# wemos_gpio.net
KiCad netlist of a schematic drawn in EAGLE
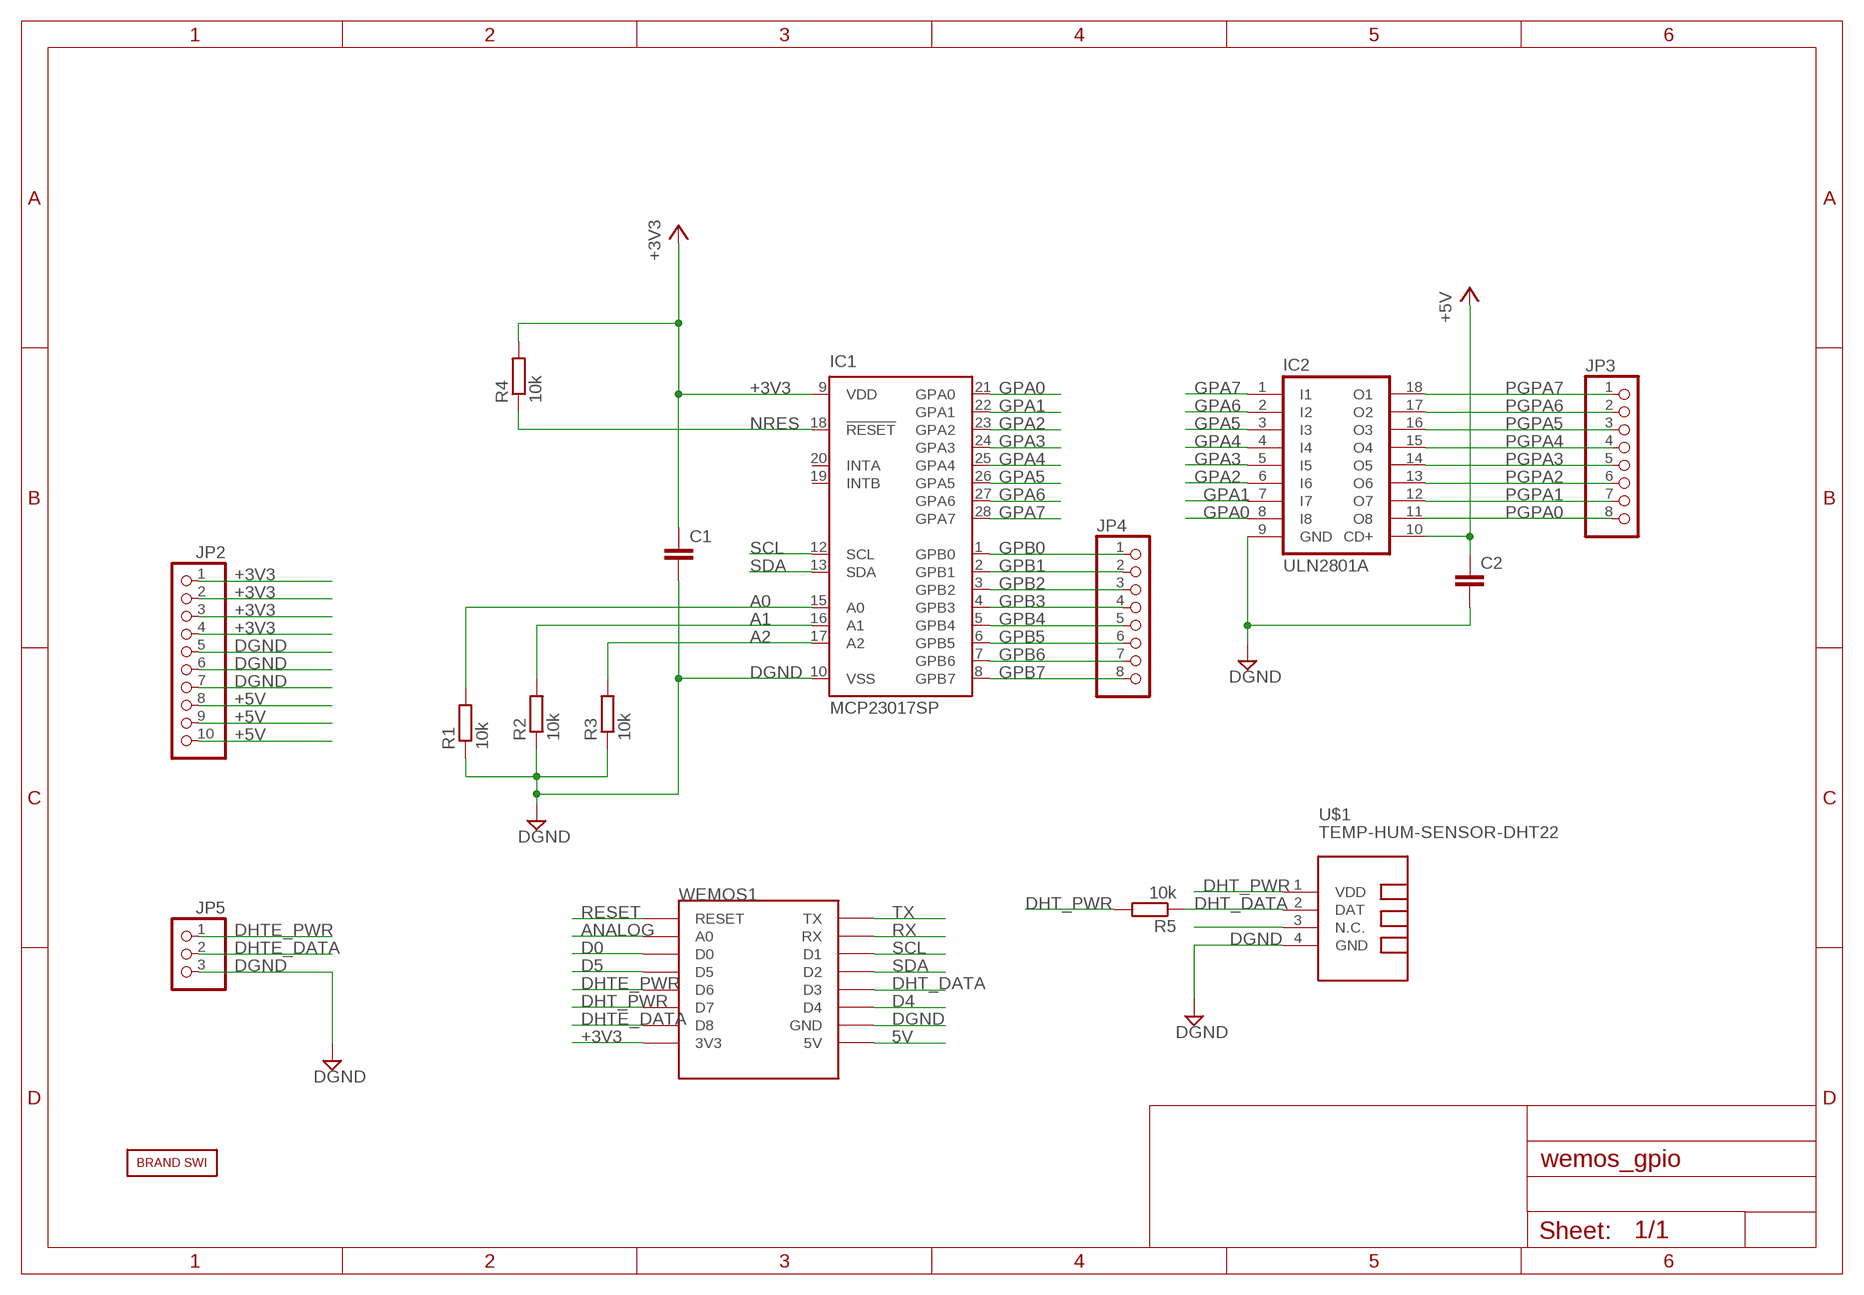
[diagram p0: schematic, sheet 1]

(export (version "E")
  (design (tool "Eeschema 10.0.6"))
  (components
    (comp (ref "C1")
      (value "C-EUC1210")
      (footprint "eagle-import:C1210")
      (libsource (lib "eagle-import") (part "C-EUC1210"))
    )
    (comp (ref "C2")
      (value "C-EUC1210")
      (footprint "eagle-import:C1210")
      (libsource (lib "eagle-import") (part "C-EUC1210"))
    )
    (comp (ref "IC1")
      (value "MCP23017SP")
      (footprint "eagle-import:DIL28-3")
      (fields (field (name "MF") "MICROCHIP") (field (name "MPN") "MCP23017-E/SP"))
      (libsource (lib "eagle-import") (part "MCP23017SP"))
    )
    (comp (ref "IC2")
      (value "ULN2801A")
      (footprint "eagle-import:DIL18")
      (libsource (lib "eagle-import") (part "ULN2801A"))
    )
    (comp (ref "JP2")
      (value "PINHD-1X10")
      (footprint "eagle-import:1X10")
      (libsource (lib "eagle-import") (part "PINHD-1X10"))
    )
    (comp (ref "JP3")
      (value "PINHD-1X8")
      (footprint "eagle-import:1X08")
      (libsource (lib "eagle-import") (part "PINHD-1X8"))
    )
    (comp (ref "JP4")
      (value "PINHD-1X8")
      (footprint "eagle-import:1X08")
      (libsource (lib "eagle-import") (part "PINHD-1X8"))
    )
    (comp (ref "JP5")
      (value "PINHD-1X3")
      (footprint "eagle-import:1X03")
      (libsource (lib "eagle-import") (part "PINHD-1X3"))
    )
    (comp (ref "R1")
      (value "10k")
      (footprint "eagle-import:M1206")
      (libsource (lib "eagle-import") (part "R-EU_M1206"))
    )
    (comp (ref "R2")
      (value "10k")
      (footprint "eagle-import:M1206")
      (libsource (lib "eagle-import") (part "R-EU_M1206"))
    )
    (comp (ref "R3")
      (value "10k")
      (footprint "eagle-import:M1206")
      (libsource (lib "eagle-import") (part "R-EU_M1206"))
    )
    (comp (ref "R4")
      (value "10k")
      (footprint "eagle-import:M1206")
      (libsource (lib "eagle-import") (part "R-EU_M1206"))
    )
    (comp (ref "R5")
      (value "10k")
      (footprint "eagle-import:M1206")
      (libsource (lib "eagle-import") (part "R-EU_M1206"))
    )
    (comp (ref "U$1")
      (value "TEMP-HUM-SENSOR-DHT22")
      (footprint "eagle-import:TEMP-HUM-SENSOR-DHT22")
      (libsource (lib "eagle-import") (part "TEMP-HUM-SENSOR-DHT22"))
    )
    (comp (ref "U$2")
      (value "BRAND_SWI5X7")
      (footprint "eagle-import:BRAND_SWI_5X7")
      (libsource (lib "eagle-import") (part "BRAND_SWI5X7"))
    )
    (comp (ref "WEMOS1")
      (value "WEMOS-D1-MINI")
      (footprint "eagle-import:WEMOS-D1-MINI")
      (libsource (lib "eagle-import") (part "WEMOS-D1-MINI"))
    )
  )
  (nets
    (net (code "1") (name "+3V3") (class "Default")
      (node (ref "C1") (pin "1") (pinfunction "1_1") (pintype "passive"))
      (node (ref "IC1") (pin "9") (pinfunction "VDD_9") (pintype "power_in"))
      (node (ref "JP2") (pin "1") (pinfunction "1_1") (pintype "passive"))
      (node (ref "JP2") (pin "2") (pinfunction "2_2") (pintype "passive"))
      (node (ref "JP2") (pin "3") (pinfunction "3_3") (pintype "passive"))
      (node (ref "JP2") (pin "4") (pinfunction "4_4") (pintype "passive"))
      (node (ref "R4") (pin "2") (pinfunction "2_2") (pintype "passive"))
      (node (ref "WEMOS1") (pin "3V3") (pinfunction "3V3_3V3") (pintype "bidirectional"))
    )
    (net (code "2") (name "+5V") (class "Default")
      (node (ref "C2") (pin "1") (pinfunction "1_1") (pintype "passive"))
      (node (ref "IC2") (pin "10") (pinfunction "CD+_10") (pintype "passive"))
      (node (ref "JP2") (pin "10") (pinfunction "10_10") (pintype "passive"))
      (node (ref "JP2") (pin "8") (pinfunction "8_8") (pintype "passive"))
      (node (ref "JP2") (pin "9") (pinfunction "9_9") (pintype "passive"))
    )
    (net (code "3") (name "/5V") (class "Default")
      (node (ref "WEMOS1") (pin "5V") (pinfunction "5V_5V") (pintype "bidirectional"))
    )
    (net (code "4") (name "/A0") (class "Default")
      (node (ref "IC1") (pin "15") (pinfunction "A0_15") (pintype "input"))
      (node (ref "R1") (pin "2") (pinfunction "2_2") (pintype "passive"))
    )
    (net (code "5") (name "/A1") (class "Default")
      (node (ref "IC1") (pin "16") (pinfunction "A1_16") (pintype "input"))
      (node (ref "R2") (pin "2") (pinfunction "2_2") (pintype "passive"))
    )
    (net (code "6") (name "/A2") (class "Default")
      (node (ref "IC1") (pin "17") (pinfunction "A2_17") (pintype "input"))
      (node (ref "R3") (pin "2") (pinfunction "2_2") (pintype "passive"))
    )
    (net (code "7") (name "/ANALOG") (class "Default")
      (node (ref "WEMOS1") (pin "A0") (pinfunction "A0_A0") (pintype "bidirectional"))
    )
    (net (code "8") (name "/D0") (class "Default")
      (node (ref "WEMOS1") (pin "D0") (pinfunction "D0_D0") (pintype "bidirectional"))
    )
    (net (code "9") (name "/D4") (class "Default")
      (node (ref "WEMOS1") (pin "D4") (pinfunction "D4_D4") (pintype "bidirectional"))
    )
    (net (code "10") (name "/D5") (class "Default")
      (node (ref "WEMOS1") (pin "D5") (pinfunction "D5_D5") (pintype "bidirectional"))
    )
    (net (code "11") (name "/DHTE_DATA") (class "Default")
      (node (ref "JP5") (pin "2") (pinfunction "2_2") (pintype "passive"))
      (node (ref "WEMOS1") (pin "D8") (pinfunction "D8_D8") (pintype "bidirectional"))
    )
    (net (code "12") (name "/DHTE_PWR") (class "Default")
      (node (ref "JP5") (pin "1") (pinfunction "1_1") (pintype "passive"))
      (node (ref "WEMOS1") (pin "D6") (pinfunction "D6_D6") (pintype "bidirectional"))
    )
    (net (code "13") (name "/DHT_DATA") (class "Default")
      (node (ref "R5") (pin "1") (pinfunction "1_1") (pintype "passive"))
      (node (ref "U$1") (pin "2") (pinfunction "DAT_2") (pintype "bidirectional"))
      (node (ref "WEMOS1") (pin "D3") (pinfunction "D3_D3") (pintype "bidirectional"))
    )
    (net (code "14") (name "/DHT_PWR") (class "Default")
      (node (ref "R5") (pin "2") (pinfunction "2_2") (pintype "passive"))
      (node (ref "U$1") (pin "1") (pinfunction "VDD_1") (pintype "power_in"))
      (node (ref "WEMOS1") (pin "D7") (pinfunction "D7_D7") (pintype "bidirectional"))
    )
    (net (code "15") (name "/GPA0") (class "Default")
      (node (ref "IC1") (pin "21") (pinfunction "GPA0_21") (pintype "bidirectional"))
      (node (ref "IC2") (pin "8") (pinfunction "I8_8") (pintype "input"))
    )
    (net (code "16") (name "/GPA1") (class "Default")
      (node (ref "IC1") (pin "22") (pinfunction "GPA1_22") (pintype "bidirectional"))
      (node (ref "IC2") (pin "7") (pinfunction "I7_7") (pintype "input"))
    )
    (net (code "17") (name "/GPA2") (class "Default")
      (node (ref "IC1") (pin "23") (pinfunction "GPA2_23") (pintype "bidirectional"))
      (node (ref "IC2") (pin "6") (pinfunction "I6_6") (pintype "input"))
    )
    (net (code "18") (name "/GPA3") (class "Default")
      (node (ref "IC1") (pin "24") (pinfunction "GPA3_24") (pintype "bidirectional"))
      (node (ref "IC2") (pin "5") (pinfunction "I5_5") (pintype "input"))
    )
    (net (code "19") (name "/GPA4") (class "Default")
      (node (ref "IC1") (pin "25") (pinfunction "GPA4_25") (pintype "bidirectional"))
      (node (ref "IC2") (pin "4") (pinfunction "I4_4") (pintype "input"))
    )
    (net (code "20") (name "/GPA5") (class "Default")
      (node (ref "IC1") (pin "26") (pinfunction "GPA5_26") (pintype "bidirectional"))
      (node (ref "IC2") (pin "3") (pinfunction "I3_3") (pintype "input"))
    )
    (net (code "21") (name "/GPA6") (class "Default")
      (node (ref "IC1") (pin "27") (pinfunction "GPA6_27") (pintype "bidirectional"))
      (node (ref "IC2") (pin "2") (pinfunction "I2_2") (pintype "input"))
    )
    (net (code "22") (name "/GPA7") (class "Default")
      (node (ref "IC1") (pin "28") (pinfunction "GPA7_28") (pintype "bidirectional"))
      (node (ref "IC2") (pin "1") (pinfunction "I1_1") (pintype "input"))
    )
    (net (code "23") (name "/GPB0") (class "Default")
      (node (ref "IC1") (pin "1") (pinfunction "GPB0_1") (pintype "bidirectional"))
      (node (ref "JP4") (pin "1") (pinfunction "1_1") (pintype "passive"))
    )
    (net (code "24") (name "/GPB1") (class "Default")
      (node (ref "IC1") (pin "2") (pinfunction "GPB1_2") (pintype "bidirectional"))
      (node (ref "JP4") (pin "2") (pinfunction "2_2") (pintype "passive"))
    )
    (net (code "25") (name "/GPB2") (class "Default")
      (node (ref "IC1") (pin "3") (pinfunction "GPB2_3") (pintype "bidirectional"))
      (node (ref "JP4") (pin "3") (pinfunction "3_3") (pintype "passive"))
    )
    (net (code "26") (name "/GPB3") (class "Default")
      (node (ref "IC1") (pin "4") (pinfunction "GPB3_4") (pintype "bidirectional"))
      (node (ref "JP4") (pin "4") (pinfunction "4_4") (pintype "passive"))
    )
    (net (code "27") (name "/GPB4") (class "Default")
      (node (ref "IC1") (pin "5") (pinfunction "GPB4_5") (pintype "bidirectional"))
      (node (ref "JP4") (pin "5") (pinfunction "5_5") (pintype "passive"))
    )
    (net (code "28") (name "/GPB5") (class "Default")
      (node (ref "IC1") (pin "6") (pinfunction "GPB5_6") (pintype "bidirectional"))
      (node (ref "JP4") (pin "6") (pinfunction "6_6") (pintype "passive"))
    )
    (net (code "29") (name "/GPB6") (class "Default")
      (node (ref "IC1") (pin "7") (pinfunction "GPB6_7") (pintype "bidirectional"))
      (node (ref "JP4") (pin "7") (pinfunction "7_7") (pintype "passive"))
    )
    (net (code "30") (name "/GPB7") (class "Default")
      (node (ref "IC1") (pin "8") (pinfunction "GPB7_8") (pintype "bidirectional"))
      (node (ref "JP4") (pin "8") (pinfunction "8_8") (pintype "passive"))
    )
    (net (code "31") (name "/NRES") (class "Default")
      (node (ref "IC1") (pin "18") (pinfunction "~{RESET}_18") (pintype "input"))
      (node (ref "R4") (pin "1") (pinfunction "1_1") (pintype "passive"))
    )
    (net (code "32") (name "/PGPA0") (class "Default")
      (node (ref "IC2") (pin "11") (pinfunction "O8_11") (pintype "open_collector"))
      (node (ref "JP3") (pin "8") (pinfunction "8_8") (pintype "passive"))
    )
    (net (code "33") (name "/PGPA1") (class "Default")
      (node (ref "IC2") (pin "12") (pinfunction "O7_12") (pintype "open_collector"))
      (node (ref "JP3") (pin "7") (pinfunction "7_7") (pintype "passive"))
    )
    (net (code "34") (name "/PGPA2") (class "Default")
      (node (ref "IC2") (pin "13") (pinfunction "O6_13") (pintype "open_collector"))
      (node (ref "JP3") (pin "6") (pinfunction "6_6") (pintype "passive"))
    )
    (net (code "35") (name "/PGPA3") (class "Default")
      (node (ref "IC2") (pin "14") (pinfunction "O5_14") (pintype "open_collector"))
      (node (ref "JP3") (pin "5") (pinfunction "5_5") (pintype "passive"))
    )
    (net (code "36") (name "/PGPA4") (class "Default")
      (node (ref "IC2") (pin "15") (pinfunction "O4_15") (pintype "open_collector"))
      (node (ref "JP3") (pin "4") (pinfunction "4_4") (pintype "passive"))
    )
    (net (code "37") (name "/PGPA5") (class "Default")
      (node (ref "IC2") (pin "16") (pinfunction "O3_16") (pintype "open_collector"))
      (node (ref "JP3") (pin "3") (pinfunction "3_3") (pintype "passive"))
    )
    (net (code "38") (name "/PGPA6") (class "Default")
      (node (ref "IC2") (pin "17") (pinfunction "O2_17") (pintype "open_collector"))
      (node (ref "JP3") (pin "2") (pinfunction "2_2") (pintype "passive"))
    )
    (net (code "39") (name "/PGPA7") (class "Default")
      (node (ref "IC2") (pin "18") (pinfunction "O1_18") (pintype "open_collector"))
      (node (ref "JP3") (pin "1") (pinfunction "1_1") (pintype "passive"))
    )
    (net (code "40") (name "/RESET") (class "Default")
      (node (ref "WEMOS1") (pin "RESET") (pinfunction "RESET_RESET") (pintype "bidirectional"))
    )
    (net (code "41") (name "/RX") (class "Default")
      (node (ref "WEMOS1") (pin "RX") (pinfunction "RX_RX") (pintype "bidirectional"))
    )
    (net (code "42") (name "/SCL") (class "Default")
      (node (ref "IC1") (pin "12") (pinfunction "SCL_12") (pintype "input"))
      (node (ref "WEMOS1") (pin "D1") (pinfunction "D1_D1") (pintype "bidirectional"))
    )
    (net (code "43") (name "/SDA") (class "Default")
      (node (ref "IC1") (pin "13") (pinfunction "SDA_13") (pintype "bidirectional"))
      (node (ref "WEMOS1") (pin "D2") (pinfunction "D2_D2") (pintype "bidirectional"))
    )
    (net (code "44") (name "/TX") (class "Default")
      (node (ref "WEMOS1") (pin "TX") (pinfunction "TX_TX") (pintype "bidirectional"))
    )
    (net (code "45") (name "DGND") (class "Default")
      (node (ref "C1") (pin "2") (pinfunction "2_2") (pintype "passive"))
      (node (ref "C2") (pin "2") (pinfunction "2_2") (pintype "passive"))
      (node (ref "IC1") (pin "10") (pinfunction "VSS_10") (pintype "power_in"))
      (node (ref "IC2") (pin "9") (pinfunction "GND_9") (pintype "power_in"))
      (node (ref "JP2") (pin "5") (pinfunction "5_5") (pintype "passive"))
      (node (ref "JP2") (pin "6") (pinfunction "6_6") (pintype "passive"))
      (node (ref "JP2") (pin "7") (pinfunction "7_7") (pintype "passive"))
      (node (ref "JP5") (pin "3") (pinfunction "3_3") (pintype "passive"))
      (node (ref "R1") (pin "1") (pinfunction "1_1") (pintype "passive"))
      (node (ref "R2") (pin "1") (pinfunction "1_1") (pintype "passive"))
      (node (ref "R3") (pin "1") (pinfunction "1_1") (pintype "passive"))
      (node (ref "U$1") (pin "4") (pinfunction "GND_4") (pintype "power_in"))
      (node (ref "WEMOS1") (pin "GND") (pinfunction "GND_GND") (pintype "bidirectional"))
    )
    (net (code "46") (name "unconnected-(IC1-INTA-Pad20)") (class "Default")
      (node (ref "IC1") (pin "20") (pinfunction "INTA_20") (pintype "output"))
    )
    (net (code "47") (name "unconnected-(IC1-INTB-Pad19)") (class "Default")
      (node (ref "IC1") (pin "19") (pinfunction "INTB_19") (pintype "output"))
    )
    (net (code "48") (name "unconnected-(U$1-N.C.-Pad3)") (class "Default")
      (node (ref "U$1") (pin "3") (pinfunction "N.C._3") (pintype "passive"))
    )
  )
)
